# ctrl_board.net
KiCad netlist of a schematic drawn in EAGLE
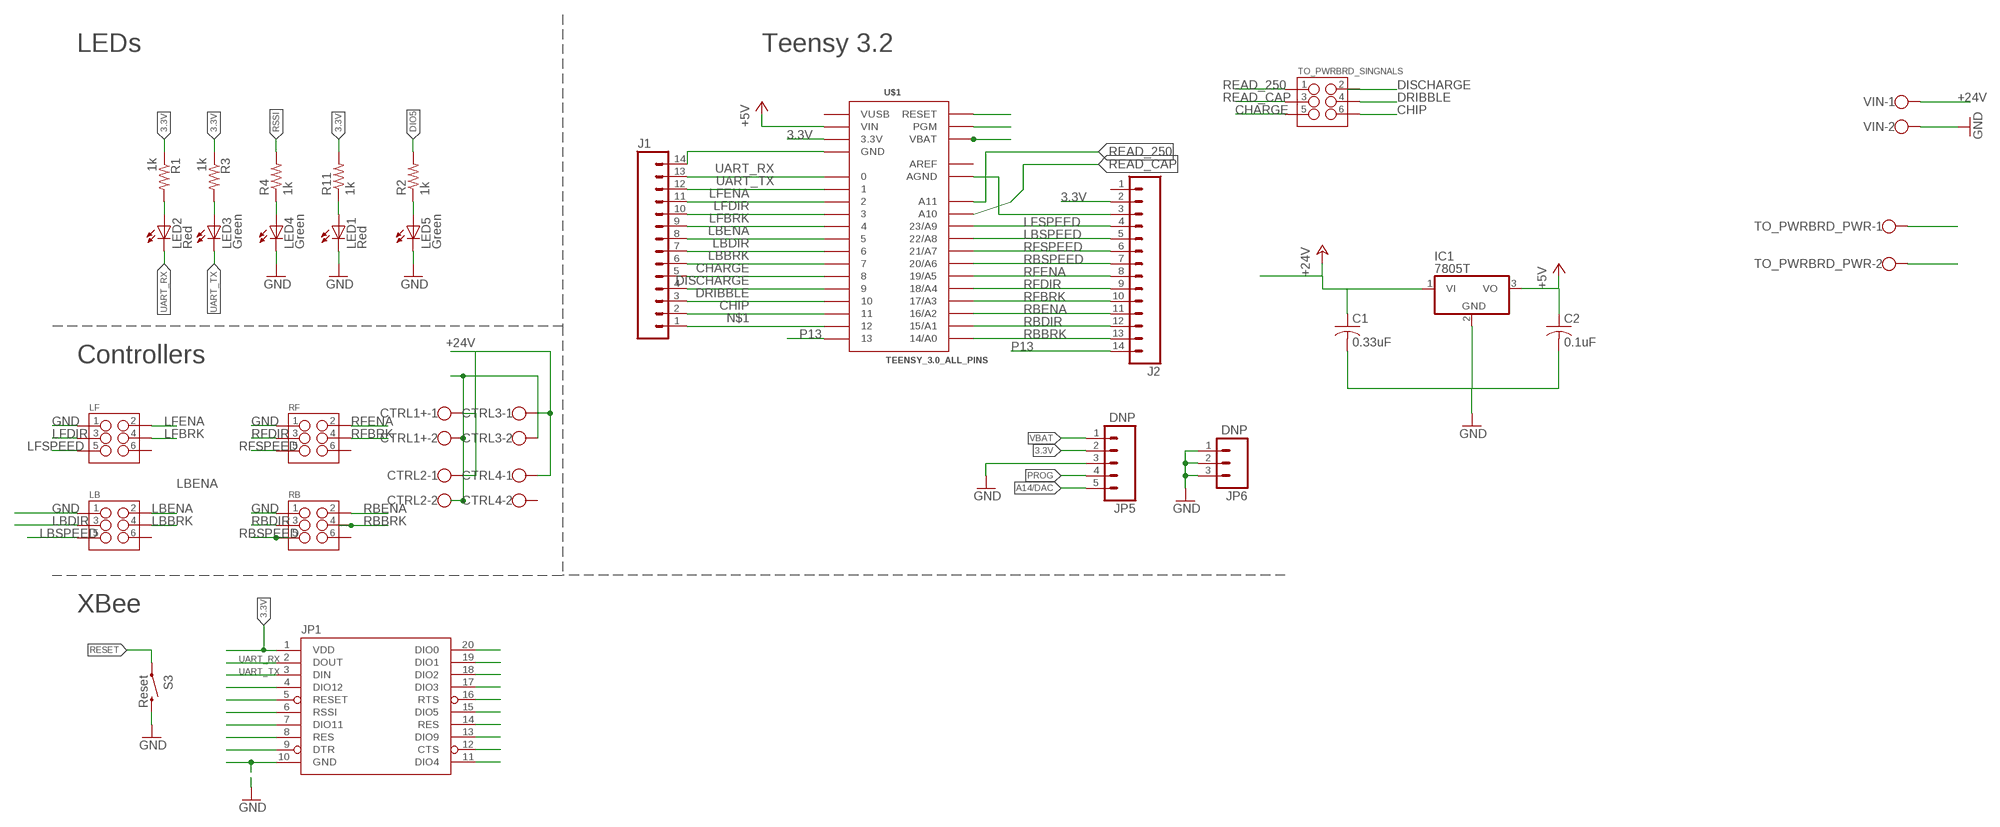
[diagram p0: schematic, sheet 1]

(export (version "E")
  (design (tool "Eeschema 10.0.6"))
  (components
    (comp (ref "C1")
      (value "0.33uF")
      (footprint "eagle-import:C0805")
      (libsource (lib "eagle-import") (part "C-USC0805"))
    )
    (comp (ref "C2")
      (value "0.1uF")
      (footprint "eagle-import:C0805")
      (libsource (lib "eagle-import") (part "C-USC0805"))
    )
    (comp (ref "CTRL1+")
      (value "W237-102")
      (footprint "eagle-import:W237-102")
      (fields (field (name "MPN") "237-102"))
      (libsource (lib "eagle-import") (part "W237-102"))
    )
    (comp (ref "CTRL2")
      (value "W237-102")
      (footprint "eagle-import:W237-102")
      (fields (field (name "MPN") "237-102"))
      (libsource (lib "eagle-import") (part "W237-102"))
    )
    (comp (ref "CTRL3")
      (value "W237-102")
      (footprint "eagle-import:W237-102")
      (fields (field (name "MPN") "237-102"))
      (libsource (lib "eagle-import") (part "W237-102"))
    )
    (comp (ref "CTRL4")
      (value "W237-102")
      (footprint "eagle-import:W237-102")
      (fields (field (name "MPN") "237-102"))
      (libsource (lib "eagle-import") (part "W237-102"))
    )
    (comp (ref "IC1")
      (value "7805T")
      (footprint "eagle-import:TO220H")
      (libsource (lib "eagle-import") (part "78T05"))
    )
    (comp (ref "J1")
      (value "M14")
      (footprint "eagle-import:1X14")
      (libsource (lib "eagle-import") (part "M14"))
    )
    (comp (ref "J2")
      (value "M14")
      (footprint "eagle-import:1X14")
      (libsource (lib "eagle-import") (part "M14"))
    )
    (comp (ref "JP1")
      (value "XBEE-1B1")
      (footprint "eagle-import:XBEE-1")
      (libsource (lib "eagle-import") (part "XBEE-1B1"))
    )
    (comp (ref "JP5")
      (value "DNP")
      (footprint "eagle-import:1X05")
      (libsource (lib "eagle-import") (part "M05PTH"))
    )
    (comp (ref "JP6")
      (value "DNP")
      (footprint "eagle-import:1X03")
      (libsource (lib "eagle-import") (part "M03PTH"))
    )
    (comp (ref "LB")
      (value "M03X2POGO_PINS")
      (footprint "eagle-import:2X3_POGO")
      (libsource (lib "eagle-import") (part "M03X2POGO_PINS"))
    )
    (comp (ref "LED1")
      (value "Red")
      (footprint "eagle-import:LED-0603")
      (libsource (lib "eagle-import") (part "LED-RED0603"))
    )
    (comp (ref "LED2")
      (value "Red")
      (footprint "eagle-import:LED-0603")
      (libsource (lib "eagle-import") (part "LED-RED0603"))
    )
    (comp (ref "LED3")
      (value "Green")
      (footprint "eagle-import:LED-0603")
      (libsource (lib "eagle-import") (part "LED-GREEN0603"))
    )
    (comp (ref "LED4")
      (value "Green")
      (footprint "eagle-import:LED-0603")
      (libsource (lib "eagle-import") (part "LED-GREEN0603"))
    )
    (comp (ref "LED5")
      (value "Green")
      (footprint "eagle-import:LED-0603")
      (libsource (lib "eagle-import") (part "LED-GREEN0603"))
    )
    (comp (ref "LF")
      (value "M03X2POGO_PINS")
      (footprint "eagle-import:2X3_POGO")
      (libsource (lib "eagle-import") (part "M03X2POGO_PINS"))
    )
    (comp (ref "R1")
      (value "1k")
      (footprint "eagle-import:0603-RES")
      (libsource (lib "eagle-import") (part "1KOHM1/10W1%(0603)"))
    )
    (comp (ref "R2")
      (value "1k")
      (footprint "eagle-import:0603-RES")
      (libsource (lib "eagle-import") (part "1KOHM1/10W1%(0603)"))
    )
    (comp (ref "R3")
      (value "1k")
      (footprint "eagle-import:0603-RES")
      (libsource (lib "eagle-import") (part "1KOHM1/10W1%(0603)"))
    )
    (comp (ref "R4")
      (value "1k")
      (footprint "eagle-import:0603-RES")
      (libsource (lib "eagle-import") (part "1KOHM1/10W1%(0603)"))
    )
    (comp (ref "R11")
      (value "1k")
      (footprint "eagle-import:0603-RES")
      (libsource (lib "eagle-import") (part "1KOHM1/10W1%(0603)"))
    )
    (comp (ref "RB")
      (value "M03X2POGO_PINS")
      (footprint "eagle-import:2X3_POGO")
      (libsource (lib "eagle-import") (part "M03X2POGO_PINS"))
    )
    (comp (ref "RF")
      (value "M03X2POGO_PINS")
      (footprint "eagle-import:2X3_POGO")
      (libsource (lib "eagle-import") (part "M03X2POGO_PINS"))
    )
    (comp (ref "S3")
      (value "Reset")
      (footprint "eagle-import:TACTILE-SWITCH-SMD")
      (libsource (lib "eagle-import") (part "SWITCH-MOMENTARY-2SMD"))
    )
    (comp (ref "TO_PWRBRD_PWR")
      (value "W237-102")
      (footprint "eagle-import:W237-102")
      (fields (field (name "MPN") "237-102"))
      (libsource (lib "eagle-import") (part "W237-102"))
    )
    (comp (ref "TO_PWRBRD_SINGNALS")
      (value "M03X2POGO_PINS")
      (footprint "eagle-import:2X3_POGO")
      (libsource (lib "eagle-import") (part "M03X2POGO_PINS"))
    )
    (comp (ref "U$1")
      (value "TEENSY_3.0_ALL_PINS")
      (footprint "eagle-import:TEENSY3-ALL_PINS")
      (libsource (lib "eagle-import") (part "TEENSY_3.0_ALL_PINS"))
    )
    (comp (ref "VIN")
      (value "W237-102")
      (footprint "eagle-import:W237-102")
      (fields (field (name "MPN") "237-102"))
      (libsource (lib "eagle-import") (part "W237-102"))
    )
  )
  (nets
    (net (code "1") (name "+5V") (class "Default")
      (node (ref "C2") (pin "1") (pinfunction "1_1") (pintype "passive"))
      (node (ref "IC1") (pin "3") (pinfunction "VO_3") (pintype "passive"))
      (node (ref "U$1") (pin "VIN") (pinfunction "VIN_VIN") (pintype "power_in"))
    )
    (net (code "2") (name "+24V") (class "Default")
      (node (ref "C1") (pin "1") (pinfunction "1_1") (pintype "passive"))
      (node (ref "CTRL3") (pin "1") (pinfunction "KL_1") (pintype "passive"))
      (node (ref "CTRL4") (pin "1") (pinfunction "KL_1") (pintype "passive"))
      (node (ref "IC1") (pin "1") (pinfunction "VI_1") (pintype "input"))
      (node (ref "TO_PWRBRD_PWR") (pin "1") (pinfunction "KL_1") (pintype "passive"))
      (node (ref "VIN") (pin "1") (pinfunction "KL_1") (pintype "passive"))
    )
    (net (code "3") (name "/AREF") (class "Default")
      (node (ref "U$1") (pin "AREF") (pinfunction "AREF_AREF") (pintype "power_in"))
    )
    (net (code "4") (name "/CHARGE") (class "Default")
      (node (ref "J1") (pin "5") (pinfunction "5_5") (pintype "passive"))
      (node (ref "TO_PWRBRD_SINGNALS") (pin "P$5") (pinfunction "5_P$5") (pintype "bidirectional"))
      (node (ref "U$1") (pin "8") (pinfunction "8_8") (pintype "bidirectional"))
    )
    (net (code "5") (name "/CHIP") (class "Default")
      (node (ref "J1") (pin "2") (pinfunction "2_2") (pintype "passive"))
      (node (ref "TO_PWRBRD_SINGNALS") (pin "P$6") (pinfunction "6_P$6") (pintype "bidirectional"))
      (node (ref "U$1") (pin "11") (pinfunction "11_11") (pintype "bidirectional"))
    )
    (net (code "6") (name "/DISCHARGE") (class "Default")
      (node (ref "J1") (pin "4") (pinfunction "4_4") (pintype "passive"))
      (node (ref "U$1") (pin "9") (pinfunction "9_9") (pintype "bidirectional"))
    )
    (net (code "7") (name "/DRIBBLE") (class "Default")
      (node (ref "J1") (pin "3") (pinfunction "3_3") (pintype "passive"))
      (node (ref "TO_PWRBRD_SINGNALS") (pin "P$4") (pinfunction "4_P$4") (pintype "bidirectional"))
      (node (ref "U$1") (pin "10") (pinfunction "10_10") (pintype "bidirectional"))
    )
    (net (code "8") (name "/LBBRK") (class "Default")
      (node (ref "J1") (pin "6") (pinfunction "6_6") (pintype "passive"))
      (node (ref "LB") (pin "P$4") (pinfunction "4_P$4") (pintype "bidirectional"))
      (node (ref "U$1") (pin "7") (pinfunction "7_7") (pintype "bidirectional"))
    )
    (net (code "9") (name "/LBDIR") (class "Default")
      (node (ref "J1") (pin "7") (pinfunction "7_7") (pintype "passive"))
      (node (ref "LB") (pin "P$3") (pinfunction "3_P$3") (pintype "bidirectional"))
      (node (ref "U$1") (pin "6") (pinfunction "6_6") (pintype "bidirectional"))
    )
    (net (code "10") (name "/LBENA") (class "Default")
      (node (ref "J1") (pin "8") (pinfunction "8_8") (pintype "passive"))
      (node (ref "LB") (pin "P$2") (pinfunction "2_P$2") (pintype "bidirectional"))
      (node (ref "U$1") (pin "5") (pinfunction "5_5") (pintype "bidirectional"))
    )
    (net (code "11") (name "/LBSPEED") (class "Default")
      (node (ref "J2") (pin "5") (pinfunction "5_5") (pintype "passive"))
      (node (ref "LB") (pin "P$5") (pinfunction "5_P$5") (pintype "bidirectional"))
      (node (ref "U$1") (pin "22/A8") (pinfunction "22/A8_22/A8") (pintype "bidirectional"))
    )
    (net (code "12") (name "/LFBRK") (class "Default")
      (node (ref "J1") (pin "9") (pinfunction "9_9") (pintype "passive"))
      (node (ref "LF") (pin "P$4") (pinfunction "4_P$4") (pintype "bidirectional"))
      (node (ref "U$1") (pin "4") (pinfunction "4_4") (pintype "bidirectional"))
    )
    (net (code "13") (name "/LFDIR") (class "Default")
      (node (ref "J1") (pin "10") (pinfunction "10_10") (pintype "passive"))
      (node (ref "LF") (pin "P$3") (pinfunction "3_P$3") (pintype "bidirectional"))
      (node (ref "U$1") (pin "3") (pinfunction "3_3") (pintype "bidirectional"))
    )
    (net (code "14") (name "/LFENA") (class "Default")
      (node (ref "J1") (pin "11") (pinfunction "11_11") (pintype "passive"))
      (node (ref "LF") (pin "P$2") (pinfunction "2_P$2") (pintype "bidirectional"))
      (node (ref "U$1") (pin "2") (pinfunction "2_2") (pintype "bidirectional"))
    )
    (net (code "15") (name "/LFSPEED") (class "Default")
      (node (ref "J2") (pin "4") (pinfunction "4_4") (pintype "passive"))
      (node (ref "LF") (pin "P$5") (pinfunction "5_P$5") (pintype "bidirectional"))
      (node (ref "U$1") (pin "23/A9") (pinfunction "23/A9_23/A9") (pintype "bidirectional"))
    )
    (net (code "16") (name "/N$1") (class "Default")
      (node (ref "J1") (pin "1") (pinfunction "1_1") (pintype "passive"))
      (node (ref "U$1") (pin "12") (pinfunction "12_12") (pintype "bidirectional"))
    )
    (net (code "17") (name "/P13") (class "Default")
      (node (ref "J2") (pin "14") (pinfunction "14_14") (pintype "passive"))
      (node (ref "U$1") (pin "13") (pinfunction "13_13") (pintype "bidirectional"))
    )
    (net (code "18") (name "/RBBRK") (class "Default")
      (node (ref "J2") (pin "13") (pinfunction "13_13") (pintype "passive"))
      (node (ref "RB") (pin "P$4") (pinfunction "4_P$4") (pintype "bidirectional"))
      (node (ref "U$1") (pin "14/A0") (pinfunction "14/A0_14/A0") (pintype "bidirectional"))
    )
    (net (code "19") (name "/RBDIR") (class "Default")
      (node (ref "J2") (pin "12") (pinfunction "12_12") (pintype "passive"))
      (node (ref "RB") (pin "P$3") (pinfunction "3_P$3") (pintype "bidirectional"))
      (node (ref "U$1") (pin "15/A1") (pinfunction "15/A1_15/A1") (pintype "bidirectional"))
    )
    (net (code "20") (name "/RBENA") (class "Default")
      (node (ref "J2") (pin "11") (pinfunction "11_11") (pintype "passive"))
      (node (ref "RB") (pin "P$2") (pinfunction "2_P$2") (pintype "bidirectional"))
      (node (ref "U$1") (pin "16/A2") (pinfunction "16/A2_16/A2") (pintype "bidirectional"))
    )
    (net (code "21") (name "/RBSPEED") (class "Default")
      (node (ref "J2") (pin "7") (pinfunction "7_7") (pintype "passive"))
      (node (ref "RB") (pin "P$5") (pinfunction "5_P$5") (pintype "bidirectional"))
      (node (ref "U$1") (pin "20/A6") (pinfunction "20/A6_20/A6") (pintype "bidirectional"))
    )
    (net (code "22") (name "/RFBRK") (class "Default")
      (node (ref "J2") (pin "10") (pinfunction "10_10") (pintype "passive"))
      (node (ref "RF") (pin "P$4") (pinfunction "4_P$4") (pintype "bidirectional"))
      (node (ref "U$1") (pin "17/A3") (pinfunction "17/A3_17/A3") (pintype "bidirectional"))
    )
    (net (code "23") (name "/RFDIR") (class "Default")
      (node (ref "J2") (pin "9") (pinfunction "9_9") (pintype "passive"))
      (node (ref "RF") (pin "P$3") (pinfunction "3_P$3") (pintype "bidirectional"))
      (node (ref "U$1") (pin "18/A4") (pinfunction "18/A4_18/A4") (pintype "bidirectional"))
    )
    (net (code "24") (name "/RFENA") (class "Default")
      (node (ref "J2") (pin "8") (pinfunction "8_8") (pintype "passive"))
      (node (ref "RF") (pin "P$2") (pinfunction "2_P$2") (pintype "bidirectional"))
      (node (ref "U$1") (pin "19/A5") (pinfunction "19/A5_19/A5") (pintype "bidirectional"))
    )
    (net (code "25") (name "/RFSPEED") (class "Default")
      (node (ref "J2") (pin "6") (pinfunction "6_6") (pintype "passive"))
      (node (ref "RF") (pin "P$5") (pinfunction "5_P$5") (pintype "bidirectional"))
      (node (ref "U$1") (pin "21/A7") (pinfunction "21/A7_21/A7") (pintype "bidirectional"))
    )
    (net (code "26") (name "/VUSB") (class "Default")
      (node (ref "U$1") (pin "VUSB") (pinfunction "VUSB_VUSB") (pintype "power_in"))
    )
    (net (code "27") (name "3.3V") (class "Default")
      (node (ref "J2") (pin "2") (pinfunction "2_2") (pintype "passive"))
      (node (ref "JP1") (pin "1") (pinfunction "VDD_1") (pintype "power_in"))
      (node (ref "JP5") (pin "2") (pinfunction "2_2") (pintype "passive"))
      (node (ref "R1") (pin "1") (pinfunction "1_1") (pintype "passive"))
      (node (ref "R11") (pin "2") (pinfunction "2_2") (pintype "passive"))
      (node (ref "R3") (pin "1") (pinfunction "1_1") (pintype "passive"))
      (node (ref "U$1") (pin "3.3V") (pinfunction "3.3V_3.3V") (pintype "power_in"))
      (node (ref "U$1") (pin "3.3V1") (pinfunction "3.3V_3.3V1") (pintype "power_in"))
    )
    (net (code "28") (name "A14{slash}DAC") (class "Default")
      (node (ref "JP5") (pin "5") (pinfunction "5_5") (pintype "passive"))
      (node (ref "U$1") (pin "RESET/DAC") (pinfunction "RESET_RESET/DAC") (pintype "bidirectional"))
    )
    (net (code "29") (name "DIO5") (class "Default")
      (node (ref "JP1") (pin "15") (pinfunction "DIO5_15") (pintype "bidirectional"))
      (node (ref "R2") (pin "2") (pinfunction "2_2") (pintype "passive"))
    )
    (net (code "30") (name "GND") (class "Default")
      (node (ref "C1") (pin "2") (pinfunction "2_2") (pintype "passive"))
      (node (ref "C2") (pin "2") (pinfunction "2_2") (pintype "passive"))
      (node (ref "CTRL1+") (pin "2") (pinfunction "KL_2") (pintype "passive"))
      (node (ref "CTRL2") (pin "2") (pinfunction "KL_2") (pintype "passive"))
      (node (ref "CTRL3") (pin "2") (pinfunction "KL_2") (pintype "passive"))
      (node (ref "IC1") (pin "2") (pinfunction "GND_2") (pintype "passive"))
      (node (ref "J1") (pin "14") (pinfunction "14_14") (pintype "passive"))
      (node (ref "JP1") (pin "10") (pinfunction "GND_10") (pintype "power_in"))
      (node (ref "JP5") (pin "3") (pinfunction "3_3") (pintype "passive"))
      (node (ref "JP6") (pin "1") (pinfunction "1_1") (pintype "passive"))
      (node (ref "JP6") (pin "2") (pinfunction "2_2") (pintype "passive"))
      (node (ref "JP6") (pin "3") (pinfunction "3_3") (pintype "passive"))
      (node (ref "LB") (pin "P$1") (pinfunction "1_P$1") (pintype "bidirectional"))
      (node (ref "LED1") (pin "C") (pinfunction "C_C") (pintype "passive"))
      (node (ref "LED4") (pin "C") (pinfunction "C_C") (pintype "passive"))
      (node (ref "LED5") (pin "C") (pinfunction "C_C") (pintype "passive"))
      (node (ref "LF") (pin "P$1") (pinfunction "1_P$1") (pintype "bidirectional"))
      (node (ref "RB") (pin "P$1") (pinfunction "1_P$1") (pintype "bidirectional"))
      (node (ref "RF") (pin "P$1") (pinfunction "1_P$1") (pintype "bidirectional"))
      (node (ref "S3") (pin "3") (pinfunction "2_3") (pintype "passive"))
      (node (ref "TO_PWRBRD_PWR") (pin "2") (pinfunction "KL_2") (pintype "passive"))
      (node (ref "U$1") (pin "GND") (pinfunction "GND_GND") (pintype "power_in"))
      (node (ref "U$1") (pin "GND1") (pinfunction "GND_GND1") (pintype "power_in"))
      (node (ref "VIN") (pin "2") (pinfunction "KL_2") (pintype "passive"))
    )
    (net (code "31") (name "Net-(CTRL1+A-KL)") (class "Default")
      (node (ref "CTRL1+") (pin "1") (pinfunction "KL_1") (pintype "passive"))
      (node (ref "CTRL2") (pin "1") (pinfunction "KL_1") (pintype "passive"))
    )
    (net (code "32") (name "Net-(J2-Pad3)") (class "Default")
      (node (ref "J2") (pin "3") (pinfunction "3_3") (pintype "passive"))
      (node (ref "U$1") (pin "AGND") (pinfunction "AGND_AGND") (pintype "power_in"))
    )
    (net (code "33") (name "Net-(LED1-PadA)") (class "Default")
      (node (ref "LED1") (pin "A") (pinfunction "A_A") (pintype "passive"))
      (node (ref "R11") (pin "1") (pinfunction "1_1") (pintype "passive"))
    )
    (net (code "34") (name "Net-(LED2-PadA)") (class "Default")
      (node (ref "LED2") (pin "A") (pinfunction "A_A") (pintype "passive"))
      (node (ref "R1") (pin "2") (pinfunction "2_2") (pintype "passive"))
    )
    (net (code "35") (name "Net-(LED3-PadA)") (class "Default")
      (node (ref "LED3") (pin "A") (pinfunction "A_A") (pintype "passive"))
      (node (ref "R3") (pin "2") (pinfunction "2_2") (pintype "passive"))
    )
    (net (code "36") (name "Net-(LED4-PadA)") (class "Default")
      (node (ref "LED4") (pin "A") (pinfunction "A_A") (pintype "passive"))
      (node (ref "R4") (pin "1") (pinfunction "1_1") (pintype "passive"))
    )
    (net (code "37") (name "Net-(LED5-PadA)") (class "Default")
      (node (ref "LED5") (pin "A") (pinfunction "A_A") (pintype "passive"))
      (node (ref "R2") (pin "1") (pinfunction "1_1") (pintype "passive"))
    )
    (net (code "38") (name "PROG") (class "Default")
      (node (ref "JP5") (pin "4") (pinfunction "4_4") (pintype "passive"))
      (node (ref "U$1") (pin "PGM") (pinfunction "PGM_PGM") (pintype "bidirectional"))
    )
    (net (code "39") (name "READ_250") (class "Default")
      (node (ref "TO_PWRBRD_SINGNALS") (pin "P$1") (pinfunction "1_P$1") (pintype "bidirectional"))
      (node (ref "U$1") (pin "A11") (pinfunction "A11_A11") (pintype "bidirectional"))
    )
    (net (code "40") (name "READ_CAP") (class "Default")
      (node (ref "TO_PWRBRD_SINGNALS") (pin "P$3") (pinfunction "3_P$3") (pintype "bidirectional"))
      (node (ref "U$1") (pin "A10") (pinfunction "A10_A10") (pintype "bidirectional"))
    )
    (net (code "41") (name "RESET") (class "Default")
      (node (ref "JP1") (pin "5") (pinfunction "RESET_5") (pintype "input"))
      (node (ref "S3") (pin "1") (pinfunction "1_1") (pintype "passive"))
    )
    (net (code "42") (name "RSSI") (class "Default")
      (node (ref "JP1") (pin "6") (pinfunction "RSSI_6") (pintype "bidirectional"))
      (node (ref "R4") (pin "2") (pinfunction "2_2") (pintype "passive"))
    )
    (net (code "43") (name "UART_RX") (class "Default")
      (node (ref "J1") (pin "13") (pinfunction "13_13") (pintype "passive"))
      (node (ref "JP1") (pin "2") (pinfunction "DOUT_2") (pintype "output"))
      (node (ref "LED2") (pin "C") (pinfunction "C_C") (pintype "passive"))
      (node (ref "U$1") (pin "0") (pinfunction "0_0") (pintype "bidirectional"))
    )
    (net (code "44") (name "UART_TX") (class "Default")
      (node (ref "J1") (pin "12") (pinfunction "12_12") (pintype "passive"))
      (node (ref "JP1") (pin "3") (pinfunction "DIN_3") (pintype "input"))
      (node (ref "LED3") (pin "C") (pinfunction "C_C") (pintype "passive"))
      (node (ref "U$1") (pin "1") (pinfunction "1_1") (pintype "bidirectional"))
    )
    (net (code "45") (name "VBAT") (class "Default")
      (node (ref "JP5") (pin "1") (pinfunction "1_1") (pintype "passive"))
      (node (ref "U$1") (pin "VBAT") (pinfunction "VBAT_VBAT") (pintype "power_in"))
    )
    (net (code "46") (name "unconnected-(CTRL4B-KL-Pad2)") (class "Default")
      (node (ref "CTRL4") (pin "2") (pinfunction "KL_2") (pintype "passive"))
    )
    (net (code "47") (name "unconnected-(J2-Pad1)") (class "Default")
      (node (ref "J2") (pin "1") (pinfunction "1_1") (pintype "passive"))
    )
    (net (code "48") (name "unconnected-(JP1-CTS-Pad12)") (class "Default")
      (node (ref "JP1") (pin "12") (pinfunction "CTS_12") (pintype "output"))
    )
    (net (code "49") (name "unconnected-(JP1-DIO0-Pad20)") (class "Default")
      (node (ref "JP1") (pin "20") (pinfunction "DIO0_20") (pintype "bidirectional"))
    )
    (net (code "50") (name "unconnected-(JP1-DIO1-Pad19)") (class "Default")
      (node (ref "JP1") (pin "19") (pinfunction "DIO1_19") (pintype "bidirectional"))
    )
    (net (code "51") (name "unconnected-(JP1-DIO2-Pad18)") (class "Default")
      (node (ref "JP1") (pin "18") (pinfunction "DIO2_18") (pintype "bidirectional"))
    )
    (net (code "52") (name "unconnected-(JP1-DIO3-Pad17)") (class "Default")
      (node (ref "JP1") (pin "17") (pinfunction "DIO3_17") (pintype "bidirectional"))
    )
    (net (code "53") (name "unconnected-(JP1-DIO4-Pad11)") (class "Default")
      (node (ref "JP1") (pin "11") (pinfunction "DIO4_11") (pintype "bidirectional"))
    )
    (net (code "54") (name "unconnected-(JP1-DIO9-Pad13)") (class "Default")
      (node (ref "JP1") (pin "13") (pinfunction "DIO9_13") (pintype "bidirectional"))
    )
    (net (code "55") (name "unconnected-(JP1-DIO11-Pad7)") (class "Default")
      (node (ref "JP1") (pin "7") (pinfunction "DIO11_7") (pintype "bidirectional"))
    )
    (net (code "56") (name "unconnected-(JP1-DIO12-Pad4)") (class "Default")
      (node (ref "JP1") (pin "4") (pinfunction "DIO12_4") (pintype "bidirectional"))
    )
    (net (code "57") (name "unconnected-(JP1-DTR-Pad9)") (class "Default")
      (node (ref "JP1") (pin "9") (pinfunction "DTR_9") (pintype "bidirectional"))
    )
    (net (code "58") (name "unconnected-(JP1-RES-Pad8)") (class "Default")
      (node (ref "JP1") (pin "8") (pinfunction "RES_8") (pintype "bidirectional"))
    )
    (net (code "59") (name "unconnected-(JP1-RES-Pad14)") (class "Default")
      (node (ref "JP1") (pin "14") (pinfunction "RES_14") (pintype "bidirectional"))
    )
    (net (code "60") (name "unconnected-(JP1-RTS-Pad16)") (class "Default")
      (node (ref "JP1") (pin "16") (pinfunction "RTS_16") (pintype "input"))
    )
    (net (code "61") (name "unconnected-(LB-6-PadP$6)") (class "Default")
      (node (ref "LB") (pin "P$6") (pinfunction "6_P$6") (pintype "bidirectional"))
    )
    (net (code "62") (name "unconnected-(LF-6-PadP$6)") (class "Default")
      (node (ref "LF") (pin "P$6") (pinfunction "6_P$6") (pintype "bidirectional"))
    )
    (net (code "63") (name "unconnected-(RB-6-PadP$6)") (class "Default")
      (node (ref "RB") (pin "P$6") (pinfunction "6_P$6") (pintype "bidirectional"))
    )
    (net (code "64") (name "unconnected-(RF-6-PadP$6)") (class "Default")
      (node (ref "RF") (pin "P$6") (pinfunction "6_P$6") (pintype "bidirectional"))
    )
    (net (code "65") (name "unconnected-(TO_PWRBRD_SINGNALS-2-PadP$2)") (class "Default")
      (node (ref "TO_PWRBRD_SINGNALS") (pin "P$2") (pinfunction "2_P$2") (pintype "bidirectional"))
    )
  )
)
